# d_main3_1.net
KiCad netlist of a schematic drawn in EAGLE
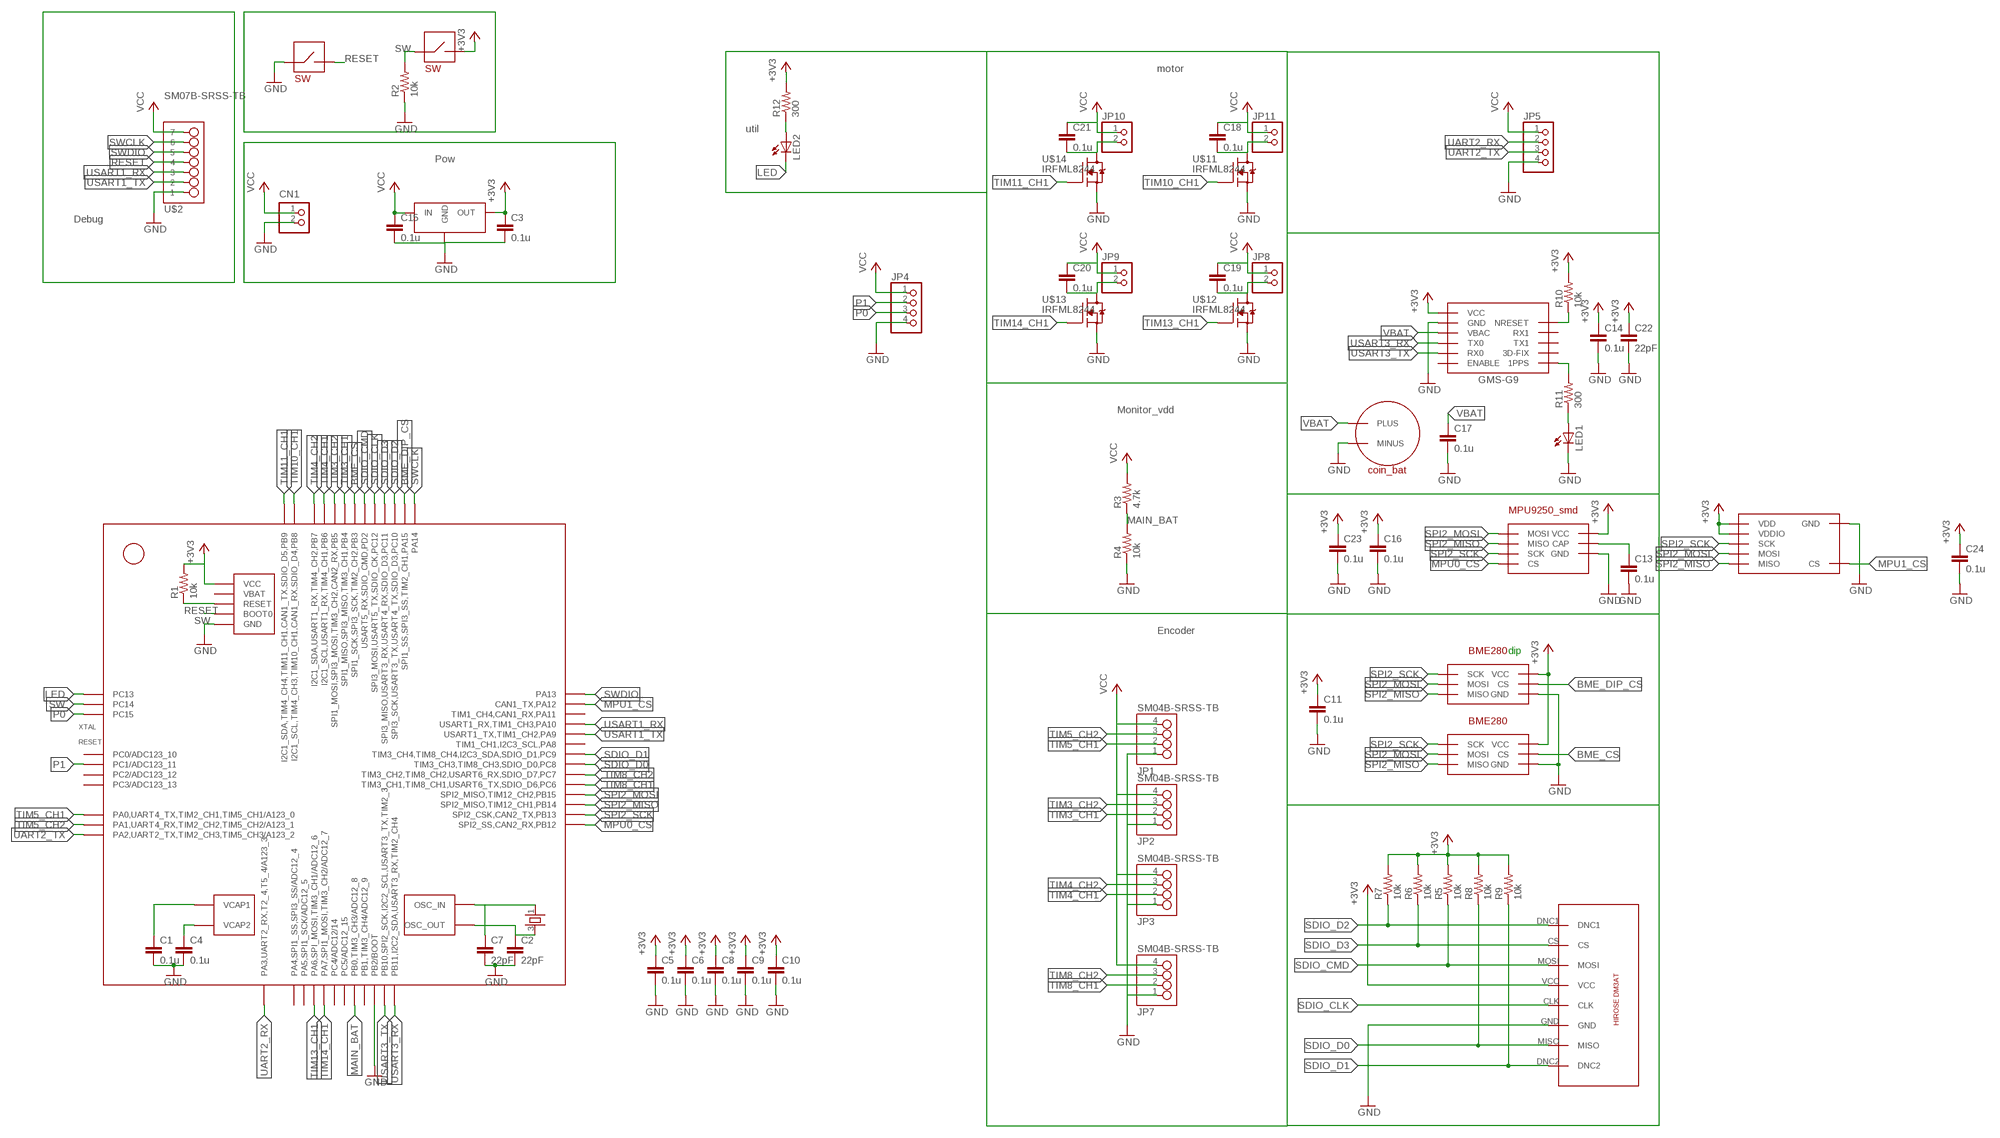
[diagram p0: schematic, sheet 1]

(export (version "E")
  (design (tool "Eeschema 10.0.6"))
  (components
    (comp (ref "C1")
      (value "0.1u")
      (footprint "eagle-import:C0603K")
      (libsource (lib "eagle-import") (part "C-EUC0603K"))
    )
    (comp (ref "C2")
      (value "22pF")
      (footprint "eagle-import:C0603K")
      (libsource (lib "eagle-import") (part "C-EUC0603K"))
    )
    (comp (ref "C3")
      (value "0.1u")
      (footprint "eagle-import:C0603K")
      (libsource (lib "eagle-import") (part "C-EUC0603K"))
    )
    (comp (ref "C4")
      (value "0.1u")
      (footprint "eagle-import:C0603K")
      (libsource (lib "eagle-import") (part "C-EUC0603K"))
    )
    (comp (ref "C5")
      (value "0.1u")
      (footprint "eagle-import:C0603K")
      (libsource (lib "eagle-import") (part "C-EUC0603K"))
    )
    (comp (ref "C6")
      (value "0.1u")
      (footprint "eagle-import:C0603K")
      (libsource (lib "eagle-import") (part "C-EUC0603K"))
    )
    (comp (ref "C7")
      (value "22pF")
      (footprint "eagle-import:C0603K")
      (libsource (lib "eagle-import") (part "C-EUC0603K"))
    )
    (comp (ref "C8")
      (value "0.1u")
      (footprint "eagle-import:C0603K")
      (libsource (lib "eagle-import") (part "C-EUC0603K"))
    )
    (comp (ref "C9")
      (value "0.1u")
      (footprint "eagle-import:C0603K")
      (libsource (lib "eagle-import") (part "C-EUC0603K"))
    )
    (comp (ref "C10")
      (value "0.1u")
      (footprint "eagle-import:C0603K")
      (libsource (lib "eagle-import") (part "C-EUC0603K"))
    )
    (comp (ref "C11")
      (value "0.1u")
      (footprint "eagle-import:C0603K")
      (libsource (lib "eagle-import") (part "C-EUC0603K"))
    )
    (comp (ref "C13")
      (value "0.1u")
      (footprint "eagle-import:C0603K")
      (libsource (lib "eagle-import") (part "C-EUC0603K"))
    )
    (comp (ref "C14")
      (value "0.1u")
      (footprint "eagle-import:C0603K")
      (libsource (lib "eagle-import") (part "C-EUC0603K"))
    )
    (comp (ref "C15")
      (value "0.1u")
      (footprint "eagle-import:C0603K")
      (libsource (lib "eagle-import") (part "C-EUC0603K"))
    )
    (comp (ref "C16")
      (value "0.1u")
      (footprint "eagle-import:C0603K")
      (libsource (lib "eagle-import") (part "C-EUC0603K"))
    )
    (comp (ref "C17")
      (value "0.1u")
      (footprint "eagle-import:C0603K")
      (libsource (lib "eagle-import") (part "C-EUC0603K"))
    )
    (comp (ref "C18")
      (value "0.1u")
      (footprint "eagle-import:C0603K")
      (libsource (lib "eagle-import") (part "C-EUC0603K"))
    )
    (comp (ref "C19")
      (value "0.1u")
      (footprint "eagle-import:C0603K")
      (libsource (lib "eagle-import") (part "C-EUC0603K"))
    )
    (comp (ref "C20")
      (value "0.1u")
      (footprint "eagle-import:C0603K")
      (libsource (lib "eagle-import") (part "C-EUC0603K"))
    )
    (comp (ref "C21")
      (value "0.1u")
      (footprint "eagle-import:C0603K")
      (libsource (lib "eagle-import") (part "C-EUC0603K"))
    )
    (comp (ref "C22")
      (value "22pF")
      (footprint "eagle-import:C0603K")
      (libsource (lib "eagle-import") (part "C-EUC0603K"))
    )
    (comp (ref "C23")
      (value "0.1u")
      (footprint "eagle-import:C0603K")
      (libsource (lib "eagle-import") (part "C-EUC0603K"))
    )
    (comp (ref "C24")
      (value "0.1u")
      (footprint "eagle-import:C0603K")
      (libsource (lib "eagle-import") (part "C-EUC0603K"))
    )
    (comp (ref "CN1")
      (value "S2B-XASK-1")
      (footprint "eagle-import:S2B-XASK-1")
      (libsource (lib "eagle-import") (part "S2B-XASK-1"))
    )
    (comp (ref "JP1")
      (value "SM04B-SRSS-TB")
      (footprint "eagle-import:SM04B-SRSS-TB")
      (libsource (lib "eagle-import") (part "SM04B-SRSS-TB"))
    )
    (comp (ref "JP2")
      (value "SM04B-SRSS-TB")
      (footprint "eagle-import:SM04B-SRSS-TB")
      (libsource (lib "eagle-import") (part "SM04B-SRSS-TB"))
    )
    (comp (ref "JP3")
      (value "SM04B-SRSS-TB")
      (footprint "eagle-import:SM04B-SRSS-TB")
      (libsource (lib "eagle-import") (part "SM04B-SRSS-TB"))
    )
    (comp (ref "JP4")
      (value "PINHD-1X4")
      (footprint "eagle-import:1X04")
      (libsource (lib "eagle-import") (part "PINHD-1X4"))
    )
    (comp (ref "JP5")
      (value "PINHD-1X4")
      (footprint "eagle-import:1X04")
      (libsource (lib "eagle-import") (part "PINHD-1X4"))
    )
    (comp (ref "JP7")
      (value "SM04B-SRSS-TB")
      (footprint "eagle-import:SM04B-SRSS-TB")
      (libsource (lib "eagle-import") (part "SM04B-SRSS-TB"))
    )
    (comp (ref "JP8")
      (value "PINHD-1X2")
      (footprint "eagle-import:1X02")
      (libsource (lib "eagle-import") (part "PINHD-1X2"))
    )
    (comp (ref "JP9")
      (value "PINHD-1X2")
      (footprint "eagle-import:1X02")
      (libsource (lib "eagle-import") (part "PINHD-1X2"))
    )
    (comp (ref "JP10")
      (value "PINHD-1X2")
      (footprint "eagle-import:1X02")
      (libsource (lib "eagle-import") (part "PINHD-1X2"))
    )
    (comp (ref "JP11")
      (value "PINHD-1X2")
      (footprint "eagle-import:1X02")
      (libsource (lib "eagle-import") (part "PINHD-1X2"))
    )
    (comp (ref "LED1")
      (value "LEDCHIP-LED0603")
      (footprint "eagle-import:CHIP-LED0603")
      (libsource (lib "eagle-import") (part "LEDCHIP-LED0603"))
    )
    (comp (ref "LED2")
      (value "LEDCHIP-LED0603")
      (footprint "eagle-import:CHIP-LED0603")
      (libsource (lib "eagle-import") (part "LEDCHIP-LED0603"))
    )
    (comp (ref "R1")
      (value "10k")
      (footprint "eagle-import:R0603")
      (libsource (lib "eagle-import") (part "R-US_R0603"))
    )
    (comp (ref "R2")
      (value "10k")
      (footprint "eagle-import:R0603")
      (libsource (lib "eagle-import") (part "R-US_R0603"))
    )
    (comp (ref "R3")
      (value "4.7k")
      (footprint "eagle-import:R0603")
      (libsource (lib "eagle-import") (part "R-US_R0603"))
    )
    (comp (ref "R4")
      (value "10k")
      (footprint "eagle-import:R0603")
      (libsource (lib "eagle-import") (part "R-US_R0603"))
    )
    (comp (ref "R5")
      (value "10k")
      (footprint "eagle-import:R0603")
      (libsource (lib "eagle-import") (part "R-US_R0603"))
    )
    (comp (ref "R6")
      (value "10k")
      (footprint "eagle-import:R0603")
      (libsource (lib "eagle-import") (part "R-US_R0603"))
    )
    (comp (ref "R7")
      (value "10k")
      (footprint "eagle-import:R0603")
      (libsource (lib "eagle-import") (part "R-US_R0603"))
    )
    (comp (ref "R8")
      (value "10k")
      (footprint "eagle-import:R0603")
      (libsource (lib "eagle-import") (part "R-US_R0603"))
    )
    (comp (ref "R9")
      (value "10k")
      (footprint "eagle-import:R0603")
      (libsource (lib "eagle-import") (part "R-US_R0603"))
    )
    (comp (ref "R10")
      (value "10k")
      (footprint "eagle-import:R0603")
      (libsource (lib "eagle-import") (part "R-US_R0603"))
    )
    (comp (ref "R11")
      (value "300")
      (footprint "eagle-import:R0603")
      (libsource (lib "eagle-import") (part "R-US_R0603"))
    )
    (comp (ref "R12")
      (value "300")
      (footprint "eagle-import:R0603")
      (libsource (lib "eagle-import") (part "R-US_R0603"))
    )
    (comp (ref "STM32F405RGT6")
      (value "STM32F405_T")
      (footprint "eagle-import:LQFP64")
      (libsource (lib "eagle-import") (part "STM32F405_T"))
    )
    (comp (ref "U$1")
      (value "GMS-G9")
      (footprint "eagle-import:GMS-G9")
      (libsource (lib "eagle-import") (part "GMS-G9"))
    )
    (comp (ref "U$2")
      (value "SM07B-SRSS-TB")
      (footprint "eagle-import:SM07B-SRSS-TB")
      (libsource (lib "eagle-import") (part "SM07B-SRSS-TB"))
    )
    (comp (ref "U$5")
      (value "DM3AT")
      (footprint "eagle-import:DM3AT")
      (libsource (lib "eagle-import") (part "DM3AT"))
    )
    (comp (ref "U$6")
      (value "SWTVBP06-B043CB-B")
      (footprint "eagle-import:SW")
      (libsource (lib "eagle-import") (part "SWTVBP06-B043CB-B"))
    )
    (comp (ref "U$7")
      (value "SWTVBP06-B043CB-B")
      (footprint "eagle-import:SW")
      (libsource (lib "eagle-import") (part "SWTVBP06-B043CB-B"))
    )
    (comp (ref "U$8")
      (value "AP7361-33E")
      (footprint "eagle-import:SOT223")
      (libsource (lib "eagle-import") (part "AP7361-33E"))
    )
    (comp (ref "U$9")
      (value "25MHz")
      (footprint "eagle-import:ASF")
      (libsource (lib "eagle-import") (part "ASF_T"))
    )
    (comp (ref "U$10")
      (value "36-3030-ND")
      (footprint "eagle-import:36-3030-ND")
      (libsource (lib "eagle-import") (part "36-3030-ND"))
    )
    (comp (ref "U$11")
      (value "IRFML8244")
      (footprint "eagle-import:SOT23")
      (libsource (lib "eagle-import") (part "IRFML8244"))
    )
    (comp (ref "U$12")
      (value "IRFML8244")
      (footprint "eagle-import:SOT23")
      (libsource (lib "eagle-import") (part "IRFML8244"))
    )
    (comp (ref "U$13")
      (value "IRFML8244")
      (footprint "eagle-import:SOT23")
      (libsource (lib "eagle-import") (part "IRFML8244"))
    )
    (comp (ref "U$14")
      (value "IRFML8244")
      (footprint "eagle-import:SOT23")
      (libsource (lib "eagle-import") (part "IRFML8244"))
    )
    (comp (ref "U$15")
      (value "MPU9250")
      (footprint "eagle-import:MPU9250_DIP")
      (libsource (lib "eagle-import") (part "MPU9250"))
    )
    (comp (ref "U$16")
      (value "MPU9250_SMD")
      (footprint "eagle-import:MPU9250_SMD")
      (libsource (lib "eagle-import") (part "MPU9250_SMD"))
    )
    (comp (ref "U$17")
      (value "BME280")
      (footprint "eagle-import:BME280")
      (libsource (lib "eagle-import") (part "BME280"))
    )
    (comp (ref "U$19")
      (value "BME280_DIP")
      (footprint "eagle-import:BME280_DIP")
      (libsource (lib "eagle-import") (part "BME280_DIP"))
    )
  )
  (nets
    (net (code "1") (name "+3V3") (class "Default")
      (node (ref "C10") (pin "1") (pinfunction "1_1") (pintype "passive"))
      (node (ref "C11") (pin "1") (pinfunction "1_1") (pintype "passive"))
      (node (ref "C14") (pin "1") (pinfunction "1_1") (pintype "passive"))
      (node (ref "C16") (pin "1") (pinfunction "1_1") (pintype "passive"))
      (node (ref "C22") (pin "1") (pinfunction "1_1") (pintype "passive"))
      (node (ref "C23") (pin "1") (pinfunction "1_1") (pintype "passive"))
      (node (ref "C24") (pin "1") (pinfunction "1_1") (pintype "passive"))
      (node (ref "C3") (pin "1") (pinfunction "1_1") (pintype "passive"))
      (node (ref "C5") (pin "1") (pinfunction "1_1") (pintype "passive"))
      (node (ref "C6") (pin "1") (pinfunction "1_1") (pintype "passive"))
      (node (ref "C8") (pin "1") (pinfunction "1_1") (pintype "passive"))
      (node (ref "C9") (pin "1") (pinfunction "1_1") (pintype "passive"))
      (node (ref "R1") (pin "2") (pinfunction "2_2") (pintype "passive"))
      (node (ref "R10") (pin "2") (pinfunction "2_2") (pintype "passive"))
      (node (ref "R12") (pin "2") (pinfunction "2_2") (pintype "passive"))
      (node (ref "R5") (pin "2") (pinfunction "2_2") (pintype "passive"))
      (node (ref "R6") (pin "2") (pinfunction "2_2") (pintype "passive"))
      (node (ref "R7") (pin "2") (pinfunction "2_2") (pintype "passive"))
      (node (ref "R8") (pin "2") (pinfunction "2_2") (pintype "passive"))
      (node (ref "R9") (pin "2") (pinfunction "2_2") (pintype "passive"))
      (node (ref "STM32F405RGT6") (pin "13") (pinfunction "VCC_13") (pintype "bidirectional"))
      (node (ref "STM32F405RGT6") (pin "19") (pinfunction "VCC_19") (pintype "bidirectional"))
      (node (ref "STM32F405RGT6") (pin "32") (pinfunction "VCC_32") (pintype "bidirectional"))
      (node (ref "STM32F405RGT6") (pin "48") (pinfunction "VCC_48") (pintype "bidirectional"))
      (node (ref "STM32F405RGT6") (pin "64") (pinfunction "VCC_64") (pintype "bidirectional"))
      (node (ref "U$1") (pin "VCC") (pinfunction "VCC_VCC") (pintype "bidirectional"))
      (node (ref "U$15") (pin "VDD") (pinfunction "VDD_VDD") (pintype "bidirectional"))
      (node (ref "U$15") (pin "VDDIO") (pinfunction "VDDIO_VDDIO") (pintype "bidirectional"))
      (node (ref "U$16") (pin "RESV") (pinfunction "VCC_RESV") (pintype "bidirectional"))
      (node (ref "U$16") (pin "VDD") (pinfunction "VCC_VDD") (pintype "bidirectional"))
      (node (ref "U$16") (pin "VDDIO") (pinfunction "VCC_VDDIO") (pintype "bidirectional"))
      (node (ref "U$17") (pin "VDD") (pinfunction "VCC_VDD") (pintype "bidirectional"))
      (node (ref "U$17") (pin "VDDIO") (pinfunction "VCC_VDDIO") (pintype "bidirectional"))
      (node (ref "U$19") (pin "VCC") (pinfunction "VCC_VCC") (pintype "bidirectional"))
      (node (ref "U$5") (pin "VCC") (pinfunction "VCC_VCC") (pintype "bidirectional"))
      (node (ref "U$7") (pin "P$2") (pinfunction "P$2_P$2") (pintype "bidirectional"))
      (node (ref "U$8") (pin "OUT") (pinfunction "OUT_OUT") (pintype "bidirectional"))
    )
    (net (code "2") (name "BME_CS") (class "Default")
      (node (ref "STM32F405RGT6") (pin "55") (pinfunction "SPI1_SCK,SPI3_SCK,TIM2_CH2,PB3_55") (pintype "bidirectional"))
      (node (ref "U$17") (pin "CS") (pinfunction "CS_CS") (pintype "bidirectional"))
    )
    (net (code "3") (name "BME_DIP_CS") (class "Default")
      (node (ref "STM32F405RGT6") (pin "50") (pinfunction "SPI1_SS,SPI3_SS,TIM2_CH1,PA15_50") (pintype "bidirectional"))
      (node (ref "U$19") (pin "CS") (pinfunction "CS_CS") (pintype "bidirectional"))
    )
    (net (code "4") (name "GND") (class "Default")
      (node (ref "C1") (pin "2") (pinfunction "2_2") (pintype "passive"))
      (node (ref "C10") (pin "2") (pinfunction "2_2") (pintype "passive"))
      (node (ref "C11") (pin "2") (pinfunction "2_2") (pintype "passive"))
      (node (ref "C13") (pin "2") (pinfunction "2_2") (pintype "passive"))
      (node (ref "C14") (pin "2") (pinfunction "2_2") (pintype "passive"))
      (node (ref "C15") (pin "2") (pinfunction "2_2") (pintype "passive"))
      (node (ref "C16") (pin "2") (pinfunction "2_2") (pintype "passive"))
      (node (ref "C17") (pin "2") (pinfunction "2_2") (pintype "passive"))
      (node (ref "C2") (pin "2") (pinfunction "2_2") (pintype "passive"))
      (node (ref "C22") (pin "2") (pinfunction "2_2") (pintype "passive"))
      (node (ref "C23") (pin "2") (pinfunction "2_2") (pintype "passive"))
      (node (ref "C24") (pin "2") (pinfunction "2_2") (pintype "passive"))
      (node (ref "C3") (pin "2") (pinfunction "2_2") (pintype "passive"))
      (node (ref "C4") (pin "2") (pinfunction "2_2") (pintype "passive"))
      (node (ref "C5") (pin "2") (pinfunction "2_2") (pintype "passive"))
      (node (ref "C6") (pin "2") (pinfunction "2_2") (pintype "passive"))
      (node (ref "C7") (pin "2") (pinfunction "2_2") (pintype "passive"))
      (node (ref "C8") (pin "2") (pinfunction "2_2") (pintype "passive"))
      (node (ref "C9") (pin "2") (pinfunction "2_2") (pintype "passive"))
      (node (ref "CN1") (pin "2") (pinfunction "2_2") (pintype "passive"))
      (node (ref "JP1") (pin "1") (pinfunction "P$1_1") (pintype "bidirectional"))
      (node (ref "JP2") (pin "1") (pinfunction "P$1_1") (pintype "bidirectional"))
      (node (ref "JP3") (pin "1") (pinfunction "P$1_1") (pintype "bidirectional"))
      (node (ref "JP4") (pin "4") (pinfunction "4_4") (pintype "passive"))
      (node (ref "JP5") (pin "4") (pinfunction "4_4") (pintype "passive"))
      (node (ref "JP7") (pin "1") (pinfunction "P$1_1") (pintype "bidirectional"))
      (node (ref "LED1") (pin "C") (pinfunction "C_C") (pintype "passive"))
      (node (ref "R2") (pin "1") (pinfunction "1_1") (pintype "passive"))
      (node (ref "R4") (pin "1") (pinfunction "1_1") (pintype "passive"))
      (node (ref "STM32F405RGT6") (pin "12") (pinfunction "GND_12") (pintype "bidirectional"))
      (node (ref "STM32F405RGT6") (pin "18") (pinfunction "GND_18") (pintype "bidirectional"))
      (node (ref "STM32F405RGT6") (pin "28") (pinfunction "PB2/BOOT_28") (pintype "bidirectional"))
      (node (ref "STM32F405RGT6") (pin "63") (pinfunction "GND_63") (pintype "bidirectional"))
      (node (ref "U$1") (pin "GND") (pinfunction "GND_GND") (pintype "bidirectional"))
      (node (ref "U$1") (pin "GND1") (pinfunction "GND_GND1") (pintype "bidirectional"))
      (node (ref "U$10") (pin "MINUS") (pinfunction "MINUS_MINUS") (pintype "bidirectional"))
      (node (ref "U$11") (pin "2") (pinfunction "S_2") (pintype "passive"))
      (node (ref "U$12") (pin "2") (pinfunction "S_2") (pintype "passive"))
      (node (ref "U$13") (pin "2") (pinfunction "S_2") (pintype "passive"))
      (node (ref "U$14") (pin "2") (pinfunction "S_2") (pintype "passive"))
      (node (ref "U$15") (pin "GND") (pinfunction "GND_GND") (pintype "bidirectional"))
      (node (ref "U$16") (pin "GND") (pinfunction "GND_GND") (pintype "bidirectional"))
      (node (ref "U$16") (pin "~RESV") (pinfunction "GND_~RESV") (pintype "bidirectional"))
      (node (ref "U$17") (pin "GND") (pinfunction "GND_GND") (pintype "bidirectional"))
      (node (ref "U$17") (pin "GND1") (pinfunction "GND_GND1") (pintype "bidirectional"))
      (node (ref "U$19") (pin "GND") (pinfunction "GND_GND") (pintype "bidirectional"))
      (node (ref "U$2") (pin "P$1") (pinfunction "1_P$1") (pintype "bidirectional"))
      (node (ref "U$5") (pin "GND") (pinfunction "GND_GND") (pintype "bidirectional"))
      (node (ref "U$6") (pin "P$1") (pinfunction "P$1_P$1") (pintype "bidirectional"))
      (node (ref "U$8") (pin "GND1") (pinfunction "GND_GND1") (pintype "bidirectional"))
      (node (ref "U$8") (pin "GND2") (pinfunction "GND_GND2") (pintype "bidirectional"))
    )
    (net (code "5") (name "LED") (class "Default")
      (node (ref "LED2") (pin "C") (pinfunction "C_C") (pintype "passive"))
      (node (ref "STM32F405RGT6") (pin "2") (pinfunction "PC13_2") (pintype "bidirectional"))
    )
    (net (code "6") (name "MAIN_BAT") (class "Default")
      (node (ref "R3") (pin "1") (pinfunction "1_1") (pintype "passive"))
      (node (ref "R4") (pin "2") (pinfunction "2_2") (pintype "passive"))
      (node (ref "STM32F405RGT6") (pin "26") (pinfunction "PB0,TIM3_CH3/ADC12_8_26") (pintype "bidirectional"))
    )
    (net (code "7") (name "MPU0_CS") (class "Default")
      (node (ref "STM32F405RGT6") (pin "33") (pinfunction "SPI2_SS,CAN2_RX,PB12_33") (pintype "bidirectional"))
      (node (ref "U$16") (pin "CS") (pinfunction "CS_CS") (pintype "bidirectional"))
    )
    (net (code "8") (name "MPU1_CS") (class "Default")
      (node (ref "STM32F405RGT6") (pin "45") (pinfunction "CAN1_TX,PA12_45") (pintype "bidirectional"))
      (node (ref "U$15") (pin "CS") (pinfunction "CS_CS") (pintype "bidirectional"))
    )
    (net (code "9") (name "Net-(LED1-PadA)") (class "Default")
      (node (ref "LED1") (pin "A") (pinfunction "A_A") (pintype "passive"))
      (node (ref "R11") (pin "1") (pinfunction "1_1") (pintype "passive"))
    )
    (net (code "10") (name "Net-(LED2-PadA)") (class "Default")
      (node (ref "LED2") (pin "A") (pinfunction "A_A") (pintype "passive"))
      (node (ref "R12") (pin "1") (pinfunction "1_1") (pintype "passive"))
    )
    (net (code "11") (name "Net-(R10-Pad1)") (class "Default")
      (node (ref "R10") (pin "1") (pinfunction "1_1") (pintype "passive"))
      (node (ref "U$1") (pin "NRESET") (pinfunction "NRESET_NRESET") (pintype "bidirectional"))
    )
    (net (code "12") (name "Net-(R11-Pad2)") (class "Default")
      (node (ref "R11") (pin "2") (pinfunction "2_2") (pintype "passive"))
      (node (ref "U$1") (pin "1PPS") (pinfunction "1PPS_1PPS") (pintype "bidirectional"))
    )
    (net (code "13") (name "Net-(STM32F405RGT6-OSC_IN)") (class "Default")
      (node (ref "C7") (pin "1") (pinfunction "1_1") (pintype "passive"))
      (node (ref "STM32F405RGT6") (pin "5") (pinfunction "OSC_IN_5") (pintype "bidirectional"))
      (node (ref "U$9") (pin "1") (pinfunction "P$1_1") (pintype "bidirectional"))
    )
    (net (code "14") (name "Net-(STM32F405RGT6-OSC_OUT)") (class "Default")
      (node (ref "C2") (pin "1") (pinfunction "1_1") (pintype "passive"))
      (node (ref "STM32F405RGT6") (pin "6") (pinfunction "OSC_OUT_6") (pintype "bidirectional"))
      (node (ref "U$9") (pin "3") (pinfunction "P$2_3") (pintype "bidirectional"))
    )
    (net (code "15") (name "Net-(STM32F405RGT6-VCAP1)") (class "Default")
      (node (ref "C1") (pin "1") (pinfunction "1_1") (pintype "passive"))
      (node (ref "STM32F405RGT6") (pin "31") (pinfunction "VCAP1_31") (pintype "bidirectional"))
    )
    (net (code "16") (name "Net-(STM32F405RGT6-VCAP2)") (class "Default")
      (node (ref "C4") (pin "1") (pinfunction "1_1") (pintype "passive"))
      (node (ref "STM32F405RGT6") (pin "47") (pinfunction "VCAP2_47") (pintype "bidirectional"))
    )
    (net (code "17") (name "Net-(U$11-D)") (class "Default")
      (node (ref "C18") (pin "2") (pinfunction "2_2") (pintype "passive"))
      (node (ref "JP11") (pin "2") (pinfunction "2_2") (pintype "passive"))
      (node (ref "U$11") (pin "3") (pinfunction "D_3") (pintype "passive"))
    )
    (net (code "18") (name "Net-(U$12-D)") (class "Default")
      (node (ref "C19") (pin "2") (pinfunction "2_2") (pintype "passive"))
      (node (ref "JP8") (pin "2") (pinfunction "2_2") (pintype "passive"))
      (node (ref "U$12") (pin "3") (pinfunction "D_3") (pintype "passive"))
    )
    (net (code "19") (name "Net-(U$13-D)") (class "Default")
      (node (ref "C20") (pin "2") (pinfunction "2_2") (pintype "passive"))
      (node (ref "JP9") (pin "2") (pinfunction "2_2") (pintype "passive"))
      (node (ref "U$13") (pin "3") (pinfunction "D_3") (pintype "passive"))
    )
    (net (code "20") (name "Net-(U$14-D)") (class "Default")
      (node (ref "C21") (pin "2") (pinfunction "2_2") (pintype "passive"))
      (node (ref "JP10") (pin "2") (pinfunction "2_2") (pintype "passive"))
      (node (ref "U$14") (pin "3") (pinfunction "D_3") (pintype "passive"))
    )
    (net (code "21") (name "Net-(U$16-CAP)") (class "Default")
      (node (ref "C13") (pin "1") (pinfunction "1_1") (pintype "passive"))
      (node (ref "U$16") (pin "REGOUT") (pinfunction "CAP_REGOUT") (pintype "bidirectional"))
    )
    (net (code "22") (name "P0") (class "Default")
      (node (ref "JP4") (pin "3") (pinfunction "3_3") (pintype "passive"))
      (node (ref "STM32F405RGT6") (pin "4") (pinfunction "PC15_4") (pintype "bidirectional"))
    )
    (net (code "23") (name "P1") (class "Default")
      (node (ref "JP4") (pin "2") (pinfunction "2_2") (pintype "passive"))
      (node (ref "STM32F405RGT6") (pin "9") (pinfunction "PC1/ADC123_11_9") (pintype "bidirectional"))
    )
    (net (code "24") (name "RESET") (class "Default")
      (node (ref "R1") (pin "1") (pinfunction "1_1") (pintype "passive"))
      (node (ref "STM32F405RGT6") (pin "7") (pinfunction "RESET_7") (pintype "bidirectional"))
      (node (ref "U$2") (pin "P$4") (pinfunction "4_P$4") (pintype "bidirectional"))
      (node (ref "U$6") (pin "P$2") (pinfunction "P$2_P$2") (pintype "bidirectional"))
    )
    (net (code "25") (name "SDIO_CLK") (class "Default")
      (node (ref "STM32F405RGT6") (pin "53") (pinfunction "SPI3_MOSI,USART5_TX,SDIO_CK,PC12_53") (pintype "bidirectional"))
      (node (ref "U$5") (pin "CLK") (pinfunction "CLK_CLK") (pintype "bidirectional"))
    )
    (net (code "26") (name "SDIO_CMD") (class "Default")
      (node (ref "R5") (pin "1") (pinfunction "1_1") (pintype "passive"))
      (node (ref "STM32F405RGT6") (pin "54") (pinfunction "USART5_RX,SDIO_CMD,PD2_54") (pintype "bidirectional"))
      (node (ref "U$5") (pin "MOSI") (pinfunction "MOSI_MOSI") (pintype "bidirectional"))
    )
    (net (code "27") (name "SDIO_D0") (class "Default")
      (node (ref "R8") (pin "1") (pinfunction "1_1") (pintype "passive"))
      (node (ref "STM32F405RGT6") (pin "39") (pinfunction "TIM3_CH3,TIM8_CH3,SDIO_D0,PC8_39") (pintype "bidirectional"))
      (node (ref "U$5") (pin "MISO") (pinfunction "MISO_MISO") (pintype "bidirectional"))
    )
    (net (code "28") (name "SDIO_D1") (class "Default")
      (node (ref "R9") (pin "1") (pinfunction "1_1") (pintype "passive"))
      (node (ref "STM32F405RGT6") (pin "40") (pinfunction "TIM3_CH4,TIM8_CH4,I2C3_SDA,SDIO_D1,PC9_40") (pintype "bidirectional"))
      (node (ref "U$5") (pin "DNC2") (pinfunction "DNC2_DNC2") (pintype "bidirectional"))
    )
    (net (code "29") (name "SDIO_D2") (class "Default")
      (node (ref "R7") (pin "1") (pinfunction "1_1") (pintype "passive"))
      (node (ref "STM32F405RGT6") (pin "51") (pinfunction "SPI3_SCK,USART3_TX,USART4_TX,SDIO_D3,PC10_51") (pintype "bidirectional"))
      (node (ref "U$5") (pin "DNC1") (pinfunction "DNC1_DNC1") (pintype "bidirectional"))
    )
    (net (code "30") (name "SDIO_D3") (class "Default")
      (node (ref "R6") (pin "1") (pinfunction "1_1") (pintype "passive"))
      (node (ref "STM32F405RGT6") (pin "52") (pinfunction "SPI3_MISO,USART3_RX,USART4_RX,SDIO_D3,PC11_52") (pintype "bidirectional"))
      (node (ref "U$5") (pin "CS") (pinfunction "CS_CS") (pintype "bidirectional"))
    )
    (net (code "31") (name "SPI2_MISO") (class "Default")
      (node (ref "STM32F405RGT6") (pin "35") (pinfunction "SPI2_MISO,TIM12_CH1,PB14_35") (pintype "bidirectional"))
      (node (ref "U$15") (pin "MISO") (pinfunction "MISO_MISO") (pintype "bidirectional"))
      (node (ref "U$16") (pin "MISO") (pinfunction "MISO_MISO") (pintype "bidirectional"))
      (node (ref "U$17") (pin "MISO") (pinfunction "MISO_MISO") (pintype "bidirectional"))
      (node (ref "U$19") (pin "MISO") (pinfunction "MISO_MISO") (pintype "bidirectional"))
    )
    (net (code "32") (name "SPI2_MOSI") (class "Default")
      (node (ref "STM32F405RGT6") (pin "36") (pinfunction "SPI2_MISO,TIM12_CH2,PB15_36") (pintype "bidirectional"))
      (node (ref "U$15") (pin "MOSI") (pinfunction "MOSI_MOSI") (pintype "bidirectional"))
      (node (ref "U$16") (pin "MOSI") (pinfunction "MOSI_MOSI") (pintype "bidirectional"))
      (node (ref "U$17") (pin "MOSI") (pinfunction "MOSI_MOSI") (pintype "bidirectional"))
      (node (ref "U$19") (pin "MOSI") (pinfunction "MOSI_MOSI") (pintype "bidirectional"))
    )
    (net (code "33") (name "SPI2_SCK") (class "Default")
      (node (ref "STM32F405RGT6") (pin "34") (pinfunction "SPI2_CSK,CAN2_TX,PB13_34") (pintype "bidirectional"))
      (node (ref "U$15") (pin "SCL") (pinfunction "SCK_SCL") (pintype "bidirectional"))
      (node (ref "U$16") (pin "SCK") (pinfunction "SCK_SCK") (pintype "bidirectional"))
      (node (ref "U$17") (pin "SCK") (pinfunction "SCK_SCK") (pintype "bidirectional"))
      (node (ref "U$19") (pin "SCK") (pinfunction "SCK_SCK") (pintype "bidirectional"))
    )
    (net (code "34") (name "SW") (class "Default")
      (node (ref "R2") (pin "2") (pinfunction "2_2") (pintype "passive"))
      (node (ref "STM32F405RGT6") (pin "3") (pinfunction "PC14_3") (pintype "bidirectional"))
      (node (ref "STM32F405RGT6") (pin "60") (pinfunction "BOOT0_60") (pintype "bidirectional"))
      (node (ref "U$7") (pin "P$1") (pinfunction "P$1_P$1") (pintype "bidirectional"))
    )
    (net (code "35") (name "SWCLK") (class "Default")
      (node (ref "STM32F405RGT6") (pin "49") (pinfunction "PA14_49") (pintype "bidirectional"))
      (node (ref "U$2") (pin "P$6") (pinfunction "6_P$6") (pintype "bidirectional"))
    )
    (net (code "36") (name "SWDIO") (class "Default")
      (node (ref "STM32F405RGT6") (pin "46") (pinfunction "PA13_46") (pintype "bidirectional"))
      (node (ref "U$2") (pin "P$5") (pinfunction "5_P$5") (pintype "bidirectional"))
    )
    (net (code "37") (name "TIM3_CH1") (class "Default")
      (node (ref "JP2") (pin "2") (pinfunction "P$2_2") (pintype "bidirectional"))
      (node (ref "STM32F405RGT6") (pin "56") (pinfunction "SPI1_MISO,SPI3_MISO,TIM3_CH1,PB4_56") (pintype "bidirectional"))
    )
    (net (code "38") (name "TIM3_CH2") (class "Default")
      (node (ref "JP2") (pin "3") (pinfunction "P$3_3") (pintype "bidirectional"))
      (node (ref "STM32F405RGT6") (pin "57") (pinfunction "SPI1_MOSI,SPI3_MOSI,TIM3_CH2,CAN2_RX,PB5_57") (pintype "bidirectional"))
    )
    (net (code "39") (name "TIM4_CH1") (class "Default")
      (node (ref "JP3") (pin "2") (pinfunction "P$2_2") (pintype "bidirectional"))
      (node (ref "STM32F405RGT6") (pin "58") (pinfunction "I2C1_SCL,USART1_RX,TIM4_CH1,PB6_58") (pintype "bidirectional"))
    )
    (net (code "40") (name "TIM4_CH2") (class "Default")
      (node (ref "JP3") (pin "3") (pinfunction "P$3_3") (pintype "bidirectional"))
      (node (ref "STM32F405RGT6") (pin "59") (pinfunction "I2C1_SDA,USART1_RX,TIM4_CH2,PB7_59") (pintype "bidirectional"))
    )
    (net (code "41") (name "TIM5_CH1") (class "Default")
      (node (ref "JP1") (pin "2") (pinfunction "P$2_2") (pintype "bidirectional"))
      (node (ref "STM32F405RGT6") (pin "14") (pinfunction "PA0,UART4_TX,TIM2_CH1,TIM5_CH1/A123_0_14") (pintype "bidirectional"))
    )
    (net (code "42") (name "TIM5_CH2") (class "Default")
      (node (ref "JP1") (pin "3") (pinfunction "P$3_3") (pintype "bidirectional"))
      (node (ref "STM32F405RGT6") (pin "15") (pinfunction "PA1,UART4_RX,TIM2_CH2,TIM5_CH2/A123_1_15") (pintype "bidirectional"))
    )
    (net (code "43") (name "TIM8_CH1") (class "Default")
      (node (ref "JP7") (pin "2") (pinfunction "P$2_2") (pintype "bidirectional"))
      (node (ref "STM32F405RGT6") (pin "37") (pinfunction "TIM3_CH1,TIM8_CH1,USART6_TX,SDIO_D6,PC6_37") (pintype "bidirectional"))
    )
    (net (code "44") (name "TIM8_CH2") (class "Default")
      (node (ref "JP7") (pin "3") (pinfunction "P$3_3") (pintype "bidirectional"))
      (node (ref "STM32F405RGT6") (pin "38") (pinfunction "TIM3_CH2,TIM8_CH2,USART6_RX,SDIO_D7,PC7_38") (pintype "bidirectional"))
    )
    (net (code "45") (name "TIM10_CH1") (class "Default")
      (node (ref "STM32F405RGT6") (pin "61") (pinfunction "I2C1_SCL,TIM4_CH3,TIM10_CH1,CAN1_RX,SDIO_D4,PB8_61") (pintype "bidirectional"))
      (node (ref "U$11") (pin "1") (pinfunction "G_1") (pintype "passive"))
    )
    (net (code "46") (name "TIM11_CH1") (class "Default")
      (node (ref "STM32F405RGT6") (pin "62") (pinfunction "I2C1_SDA,TIM4_CH4,TIM11_CH1,CAN1_TX,SDIO_D5,PB9_62") (pintype "bidirectional"))
      (node (ref "U$14") (pin "1") (pinfunction "G_1") (pintype "passive"))
    )
    (net (code "47") (name "TIM13_CH1") (class "Default")
      (node (ref "STM32F405RGT6") (pin "22") (pinfunction "PA6,SPI_MOSI,TIM3_CH1/ADC12_6_22") (pintype "bidirectional"))
      (node (ref "U$12") (pin "1") (pinfunction "G_1") (pintype "passive"))
    )
    (net (code "48") (name "TIM14_CH1") (class "Default")
      (node (ref "STM32F405RGT6") (pin "23") (pinfunction "PA7,SPI1_MOSI,TIM3_CH2/ADC12_7_23") (pintype "bidirectional"))
      (node (ref "U$13") (pin "1") (pinfunction "G_1") (pintype "passive"))
    )
    (net (code "49") (name "UART2_RX") (class "Default")
      (node (ref "JP5") (pin "2") (pinfunction "2_2") (pintype "passive"))
      (node (ref "STM32F405RGT6") (pin "17") (pinfunction "PA3,UART2_RX,T2_4,T5_4/A123_3_17") (pintype "bidirectional"))
    )
    (net (code "50") (name "UART2_TX") (class "Default")
      (node (ref "JP5") (pin "3") (pinfunction "3_3") (pintype "passive"))
      (node (ref "STM32F405RGT6") (pin "16") (pinfunction "PA2,UART2_TX,TIM2_CH3,TIM5_CH3/A123_2_16") (pintype "bidirectional"))
    )
    (net (code "51") (name "USART1_RX") (class "Default")
      (node (ref "STM32F405RGT6") (pin "43") (pinfunction "USART1_RX,TIM1_CH3,PA10_43") (pintype "bidirectional"))
      (node (ref "U$2") (pin "P$3") (pinfunction "3_P$3") (pintype "bidirectional"))
    )
    (net (code "52") (name "USART1_TX") (class "Default")
      (node (ref "STM32F405RGT6") (pin "42") (pinfunction "USART1_TX,TIM1_CH2,PA9_42") (pintype "bidirectional"))
      (node (ref "U$2") (pin "P$2") (pinfunction "2_P$2") (pintype "bidirectional"))
    )
    (net (code "53") (name "USART3_RX") (class "Default")
      (node (ref "STM32F405RGT6") (pin "30") (pinfunction "PB11,I2C2_SDA,USART3_RX,TIM2_CH4_30") (pintype "bidirectional"))
      (node (ref "U$1") (pin "TX0") (pinfunction "TX0_TX0") (pintype "bidirectional"))
    )
    (net (code "54") (name "USART3_TX") (class "Default")
      (node (ref "STM32F405RGT6") (pin "29") (pinfunction "PB10,SPI2_SCK,I2C2_SCL,USART3_TX,TIM2_3_29") (pintype "bidirectional"))
      (node (ref "U$1") (pin "RX0") (pinfunction "RX0_RX0") (pintype "bidirectional"))
    )
    (net (code "55") (name "VBAT") (class "Default")
      (node (ref "C17") (pin "1") (pinfunction "1_1") (pintype "passive"))
      (node (ref "U$1") (pin "VBAC") (pinfunction "VBAC_VBAC") (pintype "bidirectional"))
      (node (ref "U$10") (pin "PLUS1") (pinfunction "PLUS_PLUS1") (pintype "bidirectional"))
      (node (ref "U$10") (pin "PLUS2") (pinfunction "PLUS_PLUS2") (pintype "bidirectional"))
    )
    (net (code "56") (name "VCC") (class "Default")
      (node (ref "C15") (pin "1") (pinfunction "1_1") (pintype "passive"))
      (node (ref "C18") (pin "1") (pinfunction "1_1") (pintype "passive"))
      (node (ref "C19") (pin "1") (pinfunction "1_1") (pintype "passive"))
      (node (ref "C20") (pin "1") (pinfunction "1_1") (pintype "passive"))
      (node (ref "C21") (pin "1") (pinfunction "1_1") (pintype "passive"))
      (node (ref "CN1") (pin "1") (pinfunction "1_1") (pintype "passive"))
      (node (ref "JP1") (pin "4") (pinfunction "P$4_4") (pintype "bidirectional"))
      (node (ref "JP10") (pin "1") (pinfunction "1_1") (pintype "passive"))
      (node (ref "JP11") (pin "1") (pinfunction "1_1") (pintype "passive"))
      (node (ref "JP2") (pin "4") (pinfunction "P$4_4") (pintype "bidirectional"))
      (node (ref "JP3") (pin "4") (pinfunction "P$4_4") (pintype "bidirectional"))
      (node (ref "JP4") (pin "1") (pinfunction "1_1") (pintype "passive"))
      (node (ref "JP5") (pin "1") (pinfunction "1_1") (pintype "passive"))
      (node (ref "JP7") (pin "4") (pinfunction "P$4_4") (pintype "bidirectional"))
      (node (ref "JP8") (pin "1") (pinfunction "1_1") (pintype "passive"))
      (node (ref "JP9") (pin "1") (pinfunction "1_1") (pintype "passive"))
      (node (ref "R3") (pin "2") (pinfunction "2_2") (pintype "passive"))
      (node (ref "U$2") (pin "P$7") (pinfunction "7_P$7") (pintype "bidirectional"))
      (node (ref "U$8") (pin "IN") (pinfunction "IN_IN") (pintype "bidirectional"))
    )
    (net (code "57") (name "unconnected-(STM32F405RGT6-PA4,SPI1_SS,SPI3_SS{slash}ADC12_4-Pad20)") (class "Default")
      (node (ref "STM32F405RGT6") (pin "20") (pinfunction "PA4,SPI1_SS,SPI3_SS/ADC12_4_20") (pintype "bidirectional"))
    )
    (net (code "58") (name "unconnected-(STM32F405RGT6-PA5,SPI1_SCK{slash}ADC12_5-Pad21)") (class "Default")
      (node (ref "STM32F405RGT6") (pin "21") (pinfunction "PA5,SPI1_SCK/ADC12_5_21") (pintype "bidirectional"))
    )
    (net (code "59") (name "unconnected-(STM32F405RGT6-PB1,TIM3_CH4{slash}ADC12_9-Pad27)") (class "Default")
      (node (ref "STM32F405RGT6") (pin "27") (pinfunction "PB1,TIM3_CH4/ADC12_9_27") (pintype "bidirectional"))
    )
    (net (code "60") (name "unconnected-(STM32F405RGT6-PC0{slash}ADC123_10-Pad8)") (class "Default")
      (node (ref "STM32F405RGT6") (pin "8") (pinfunction "PC0/ADC123_10_8") (pintype "bidirectional"))
    )
    (net (code "61") (name "unconnected-(STM32F405RGT6-PC2{slash}ADC123_12-Pad10)") (class "Default")
      (node (ref "STM32F405RGT6") (pin "10") (pinfunction "PC2/ADC123_12_10") (pintype "bidirectional"))
    )
    (net (code "62") (name "unconnected-(STM32F405RGT6-PC3{slash}ADC123_13-Pad11)") (class "Default")
      (node (ref "STM32F405RGT6") (pin "11") (pinfunction "PC3/ADC123_13_11") (pintype "bidirectional"))
    )
    (net (code "63") (name "unconnected-(STM32F405RGT6-PC4{slash}ADC12{slash}14-Pad24)") (class "Default")
      (node (ref "STM32F405RGT6") (pin "24") (pinfunction "PC4/ADC12/14_24") (pintype "bidirectional"))
    )
    (net (code "64") (name "unconnected-(STM32F405RGT6-PC5{slash}ADC12_15-Pad25)") (class "Default")
      (node (ref "STM32F405RGT6") (pin "25") (pinfunction "PC5/ADC12_15_25") (pintype "bidirectional"))
    )
    (net (code "65") (name "unconnected-(STM32F405RGT6-TIM1_CH1,I2C3_SCL,PA8-Pad41)") (class "Default")
      (node (ref "STM32F405RGT6") (pin "41") (pinfunction "TIM1_CH1,I2C3_SCL,PA8_41") (pintype "bidirectional"))
    )
    (net (code "66") (name "unconnected-(STM32F405RGT6-TIM1_CH4,CAN1_RX,PA11-Pad44)") (class "Default")
      (node (ref "STM32F405RGT6") (pin "44") (pinfunction "TIM1_CH4,CAN1_RX,PA11_44") (pintype "bidirectional"))
    )
    (net (code "67") (name "unconnected-(STM32F405RGT6-VBAT-Pad1)") (class "Default")
      (node (ref "STM32F405RGT6") (pin "1") (pinfunction "VBAT_1") (pintype "bidirectional"))
    )
    (net (code "68") (name "unconnected-(U$1-Pad3D-FIX)") (class "Default")
      (node (ref "U$1") (pin "3D-FIX") (pinfunction "3D-FIX_3D-FIX") (pintype "bidirectional"))
    )
    (net (code "69") (name "unconnected-(U$1-PadENABLE)") (class "Default")
      (node (ref "U$1") (pin "ENABLE") (pinfunction "ENABLE_ENABLE") (pintype "bidirectional"))
    )
    (net (code "70") (name "unconnected-(U$1-PadRX1)") (class "Default")
      (node (ref "U$1") (pin "RX1") (pinfunction "RX1_RX1") (pintype "bidirectional"))
    )
    (net (code "71") (name "unconnected-(U$1-PadTX1)") (class "Default")
      (node (ref "U$1") (pin "TX1") (pinfunction "TX1_TX1") (pintype "bidirectional"))
    )
  )
)
